# SparkFun_TMC6300_Breakout-BottomJig.net
KiCad netlist of a schematic drawn in EAGLE
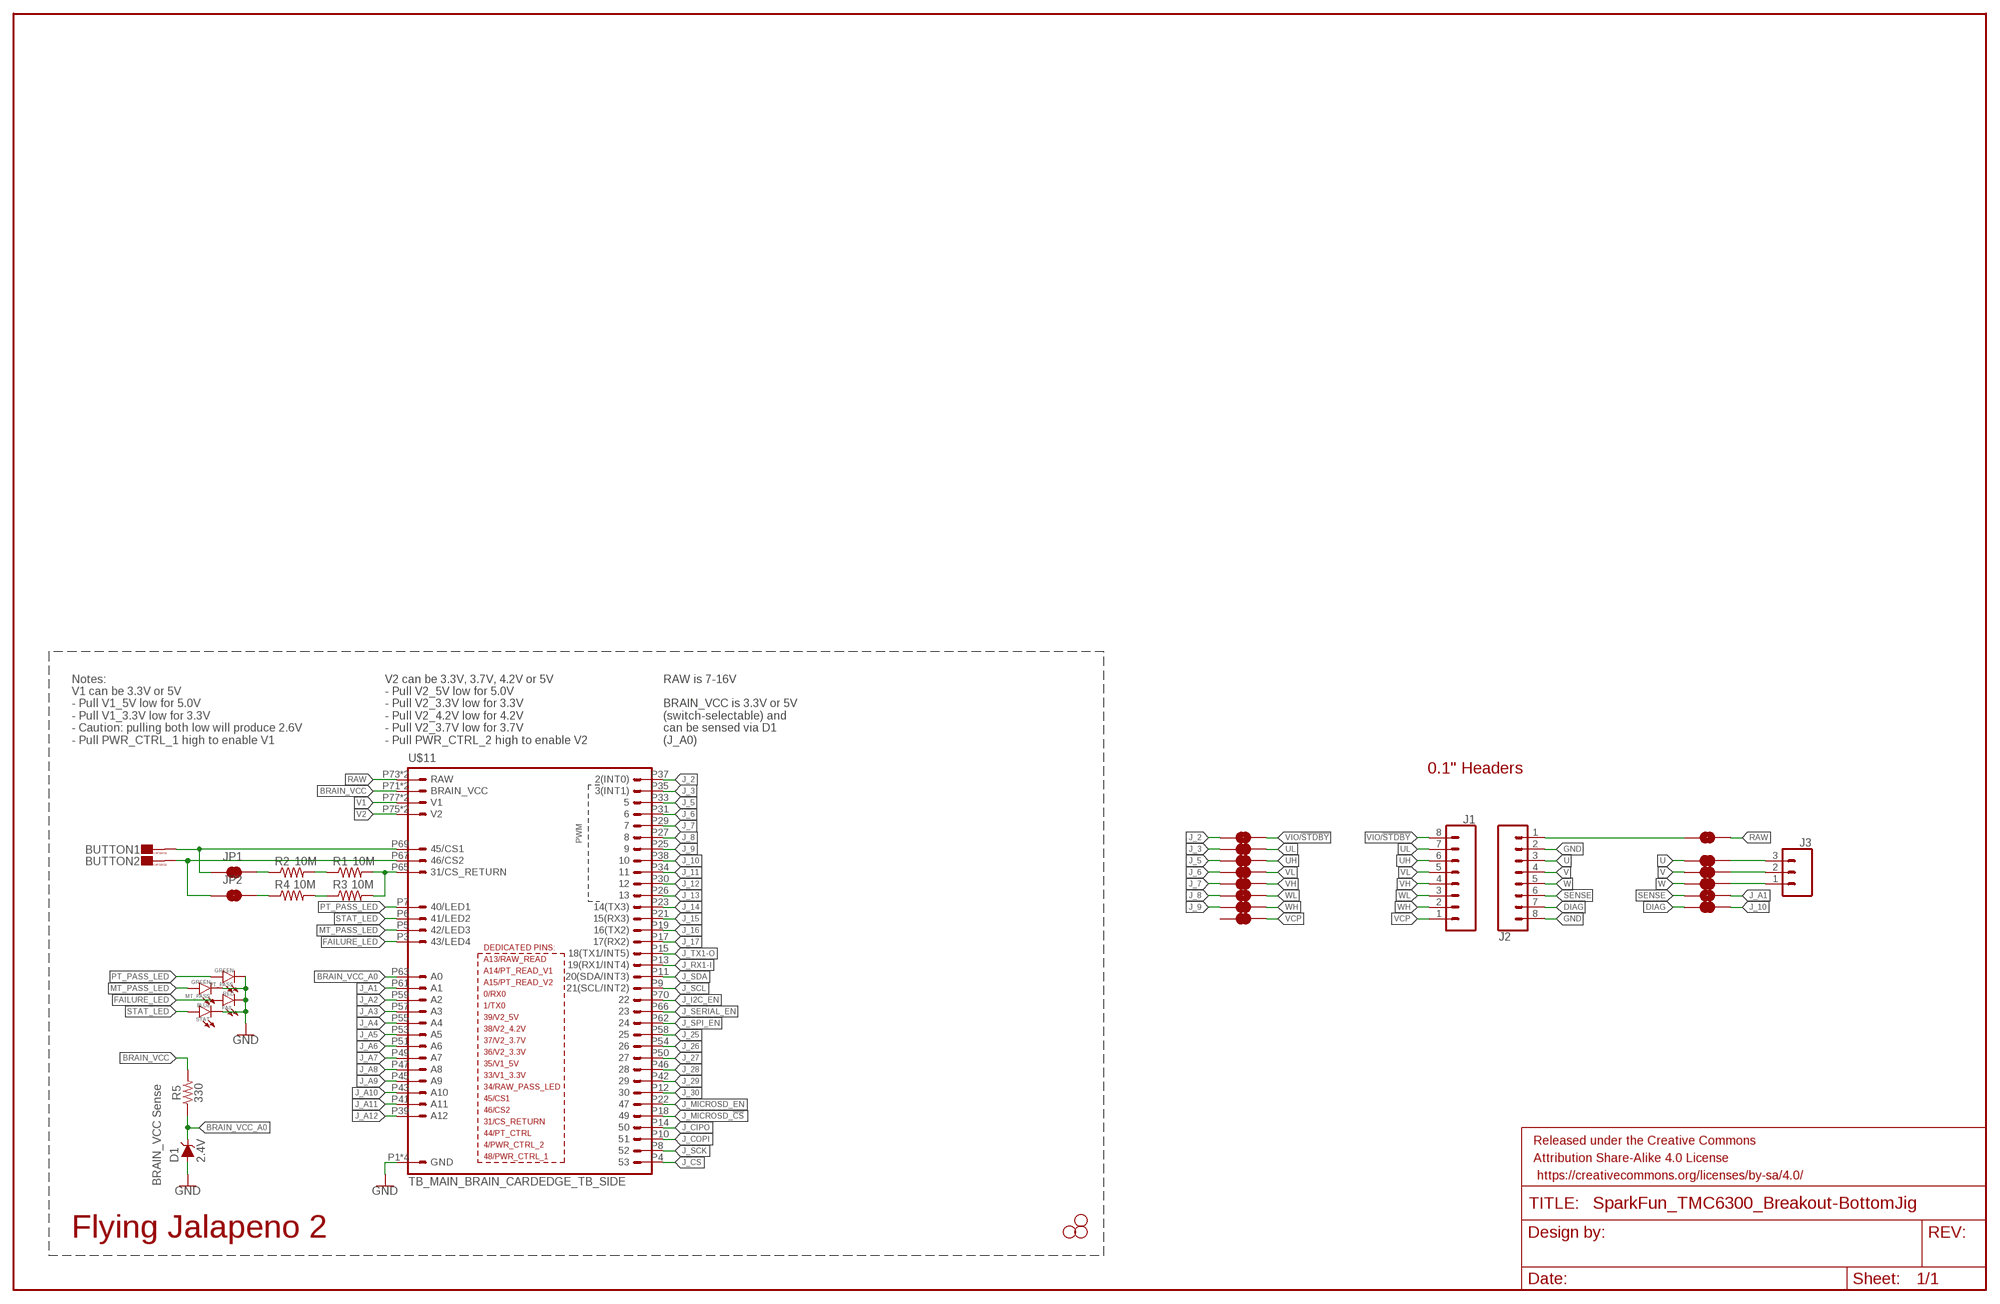
[diagram p0: schematic, sheet 1]

(export (version "E")
  (design (tool "Eeschema 10.0.6"))
  (components
    (comp (ref "BUTTON1")
      (value "CAPSENSE_BUTTON_PAD_ONLYV2_SMALL")
      (footprint "eagle-import:CAPSENSE_BUTTON_PAD_ONLY_SM")
      (libsource (lib "eagle-import") (part "CAPSENSE_BUTTON_PAD_ONLYV2_SMALL"))
    )
    (comp (ref "BUTTON2")
      (value "CAPSENSE_BUTTON_PAD_ONLYV2_SMALL")
      (footprint "eagle-import:CAPSENSE_BUTTON_PAD_ONLY_SM")
      (libsource (lib "eagle-import") (part "CAPSENSE_BUTTON_PAD_ONLYV2_SMALL"))
    )
    (comp (ref "D1")
      (value "2.4V")
      (footprint "eagle-import:SOD-323")
      (fields (field (name "DIGIKEY_PART") "MM3Z2V4T1GOSCT-ND"))
      (libsource (lib "eagle-import") (part "DIODE-ZENER-MM3Z2V4T1G"))
    )
    (comp (ref "FAIL")
      (value "RED")
      (footprint "eagle-import:LED-1206")
      (libsource (lib "eagle-import") (part "LED-RED1206"))
    )
    (comp (ref "FRAME2")
      (value "FRAME-LEDGER")
      (footprint "eagle-import:CREATIVE_COMMONS")
      (libsource (lib "eagle-import") (part "FRAME-LEDGER"))
    )
    (comp (ref "H1")
      (value "STAND-OFF")
      (footprint "eagle-import:STAND-OFF")
      (libsource (lib "eagle-import") (part "STAND-OFF"))
    )
    (comp (ref "H3")
      (value "STAND-OFF")
      (footprint "eagle-import:STAND-OFF")
      (libsource (lib "eagle-import") (part "STAND-OFF"))
    )
    (comp (ref "H4")
      (value "STAND-OFF")
      (footprint "eagle-import:STAND-OFF")
      (libsource (lib "eagle-import") (part "STAND-OFF"))
    )
    (comp (ref "J1")
      (value "CONN_08LOCK_NO_SILK")
      (footprint "eagle-import:1X08_LOCK_NO_SILK")
      (libsource (lib "eagle-import") (part "CONN_08LOCK_NO_SILK"))
    )
    (comp (ref "J2")
      (value "CONN_08LOCK_NO_SILK")
      (footprint "eagle-import:1X08_LOCK_NO_SILK")
      (libsource (lib "eagle-import") (part "CONN_08LOCK_NO_SILK"))
    )
    (comp (ref "J3")
      (value "CONN_031X03_NO_SILK")
      (footprint "eagle-import:1X03_NO_SILK")
      (libsource (lib "eagle-import") (part "CONN_031X03_NO_SILK"))
    )
    (comp (ref "JP1")
      (value "JUMPER-SMT_2_NC_TRACE_SILK")
      (footprint "eagle-import:SMT-JUMPER_2_NC_TRACE_SILK")
      (libsource (lib "eagle-import") (part "JUMPER-SMT_2_NC_TRACE_SILK"))
    )
    (comp (ref "JP2")
      (value "JUMPER-SMT_2_NC_TRACE_SILK")
      (footprint "eagle-import:SMT-JUMPER_2_NC_TRACE_SILK")
      (libsource (lib "eagle-import") (part "JUMPER-SMT_2_NC_TRACE_SILK"))
    )
    (comp (ref "J_SCL6")
      (value "JUMPER-SMT_2_NC_TRACE_NO-SILK")
      (footprint "eagle-import:SMT-JUMPER_2_NC_TRACE_NO-SILK")
      (libsource (lib "eagle-import") (part "JUMPER-SMT_2_NC_TRACE_NO-SILK"))
    )
    (comp (ref "J_SCL7")
      (value "JUMPER-SMT_2_NC_TRACE_NO-SILK")
      (footprint "eagle-import:SMT-JUMPER_2_NC_TRACE_NO-SILK")
      (libsource (lib "eagle-import") (part "JUMPER-SMT_2_NC_TRACE_NO-SILK"))
    )
    (comp (ref "J_SCL8")
      (value "JUMPER-SMT_2_NC_TRACE_NO-SILK")
      (footprint "eagle-import:SMT-JUMPER_2_NC_TRACE_NO-SILK")
      (libsource (lib "eagle-import") (part "JUMPER-SMT_2_NC_TRACE_NO-SILK"))
    )
    (comp (ref "J_SDA1")
      (value "JUMPER-SMT_2_NC_TRACE_NO-SILK")
      (footprint "eagle-import:SMT-JUMPER_2_NC_TRACE_NO-SILK")
      (libsource (lib "eagle-import") (part "JUMPER-SMT_2_NC_TRACE_NO-SILK"))
    )
    (comp (ref "J_SDA2")
      (value "JUMPER-SMT_2_NC_TRACE_NO-SILK")
      (footprint "eagle-import:SMT-JUMPER_2_NC_TRACE_NO-SILK")
      (libsource (lib "eagle-import") (part "JUMPER-SMT_2_NC_TRACE_NO-SILK"))
    )
    (comp (ref "J_SDA3")
      (value "JUMPER-SMT_2_NC_TRACE_NO-SILK")
      (footprint "eagle-import:SMT-JUMPER_2_NC_TRACE_NO-SILK")
      (libsource (lib "eagle-import") (part "JUMPER-SMT_2_NC_TRACE_NO-SILK"))
    )
    (comp (ref "J_SDA4")
      (value "JUMPER-SMT_2_NC_TRACE_NO-SILK")
      (footprint "eagle-import:SMT-JUMPER_2_NC_TRACE_NO-SILK")
      (libsource (lib "eagle-import") (part "JUMPER-SMT_2_NC_TRACE_NO-SILK"))
    )
    (comp (ref "J_SDA5")
      (value "JUMPER-SMT_2_NC_TRACE_NO-SILK")
      (footprint "eagle-import:SMT-JUMPER_2_NC_TRACE_NO-SILK")
      (libsource (lib "eagle-import") (part "JUMPER-SMT_2_NC_TRACE_NO-SILK"))
    )
    (comp (ref "J_SDA6")
      (value "JUMPER-SMT_2_NC_TRACE_NO-SILK")
      (footprint "eagle-import:SMT-JUMPER_2_NC_TRACE_NO-SILK")
      (libsource (lib "eagle-import") (part "JUMPER-SMT_2_NC_TRACE_NO-SILK"))
    )
    (comp (ref "J_SDA7")
      (value "JUMPER-SMT_2_NC_TRACE_NO-SILK")
      (footprint "eagle-import:SMT-JUMPER_2_NC_TRACE_NO-SILK")
      (libsource (lib "eagle-import") (part "JUMPER-SMT_2_NC_TRACE_NO-SILK"))
    )
    (comp (ref "J_SDA8")
      (value "JUMPER-SMT_2_NC_TRACE_NO-SILK")
      (footprint "eagle-import:SMT-JUMPER_2_NC_TRACE_NO-SILK")
      (libsource (lib "eagle-import") (part "JUMPER-SMT_2_NC_TRACE_NO-SILK"))
    )
    (comp (ref "J_SDA9")
      (value "JUMPER-SMT_2_NC_TRACE_NO-SILK")
      (footprint "eagle-import:SMT-JUMPER_2_NC_TRACE_NO-SILK")
      (libsource (lib "eagle-import") (part "JUMPER-SMT_2_NC_TRACE_NO-SILK"))
    )
    (comp (ref "J_SDA10")
      (value "JUMPER-SMT_2_NC_TRACE_NO-SILK")
      (footprint "eagle-import:SMT-JUMPER_2_NC_TRACE_NO-SILK")
      (libsource (lib "eagle-import") (part "JUMPER-SMT_2_NC_TRACE_NO-SILK"))
    )
    (comp (ref "J_SDA11")
      (value "JUMPER-SMT_2_NC_TRACE_NO-SILK")
      (footprint "eagle-import:SMT-JUMPER_2_NC_TRACE_NO-SILK")
      (libsource (lib "eagle-import") (part "JUMPER-SMT_2_NC_TRACE_NO-SILK"))
    )
    (comp (ref "MT_PASS")
      (value "GREEN")
      (footprint "eagle-import:LED-1206")
      (libsource (lib "eagle-import") (part "LED-GREEN1206"))
    )
    (comp (ref "PT_PASS")
      (value "GREEN")
      (footprint "eagle-import:LED-1206")
      (libsource (lib "eagle-import") (part "LED-GREEN1206"))
    )
    (comp (ref "R1")
      (value "10M")
      (footprint "eagle-import:0603")
      (libsource (lib "eagle-import") (part "10MOHM-0603-1/10W-5%"))
    )
    (comp (ref "R2")
      (value "10M")
      (footprint "eagle-import:0603")
      (libsource (lib "eagle-import") (part "10MOHM-0603-1/10W-5%"))
    )
    (comp (ref "R3")
      (value "10M")
      (footprint "eagle-import:0603")
      (libsource (lib "eagle-import") (part "10MOHM-0603-1/10W-5%"))
    )
    (comp (ref "R4")
      (value "10M")
      (footprint "eagle-import:0603")
      (libsource (lib "eagle-import") (part "10MOHM-0603-1/10W-5%"))
    )
    (comp (ref "R5")
      (value "330")
      (footprint "eagle-import:0603")
      (libsource (lib "eagle-import") (part "330OHM-0603-1/10W-1%"))
    )
    (comp (ref "STAT")
      (value "BLUE")
      (footprint "eagle-import:LED-1206")
      (libsource (lib "eagle-import") (part "LED-BLUE1206"))
    )
    (comp (ref "U$11")
      (value "TB_MAIN_BRAIN_CARDEDGE_TB_SIDE")
      (footprint "eagle-import:TB_CARDEDGE")
      (libsource (lib "eagle-import") (part "TB_MAIN_BRAIN_CARDEDGE_TB_SIDE"))
    )
  )
  (nets
    (net (code "1") (name "/J_MICROSD_~{CS}") (class "Default")
      (node (ref "U$11") (pin "P18") (pinfunction "49_P18") (pintype "passive"))
    )
    (net (code "2") (name "/VIO{slash}~{STDBY}") (class "Default")
      (node (ref "J1") (pin "8") (pinfunction "8_8") (pintype "passive"))
      (node (ref "J_SCL8") (pin "2") (pinfunction "2_2") (pintype "passive"))
    )
    (net (code "3") (name "BRAIN_VCC") (class "Default")
      (node (ref "R5") (pin "2") (pinfunction "2_2") (pintype "passive"))
      (node (ref "U$11") (pin "P71") (pinfunction "BRAIN_VCC_P71") (pintype "passive"))
      (node (ref "U$11") (pin "P72") (pinfunction "BRAIN_VCC_P72") (pintype "passive"))
    )
    (net (code "4") (name "BRAIN_VCC_A0") (class "Default")
      (node (ref "D1") (pin "C") (pinfunction "C_C") (pintype "passive"))
      (node (ref "R5") (pin "1") (pinfunction "1_1") (pintype "passive"))
      (node (ref "U$11") (pin "P63") (pinfunction "A0_P63") (pintype "passive"))
    )
    (net (code "5") (name "DIAG") (class "Default")
      (node (ref "J2") (pin "7") (pinfunction "7_7") (pintype "passive"))
      (node (ref "J_SDA7") (pin "1") (pinfunction "1_1") (pintype "passive"))
    )
    (net (code "6") (name "FAILURE_LED") (class "Default")
      (node (ref "FAIL") (pin "A") (pinfunction "A_A") (pintype "passive"))
      (node (ref "U$11") (pin "P3") (pinfunction "43/LED4_P3") (pintype "passive"))
    )
    (net (code "7") (name "GND") (class "Default")
      (node (ref "D1") (pin "A") (pinfunction "A_A") (pintype "passive"))
      (node (ref "FAIL") (pin "C") (pinfunction "C_C") (pintype "passive"))
      (node (ref "J2") (pin "2") (pinfunction "2_2") (pintype "passive"))
      (node (ref "J2") (pin "8") (pinfunction "8_8") (pintype "passive"))
      (node (ref "MT_PASS") (pin "C") (pinfunction "C_C") (pintype "passive"))
      (node (ref "PT_PASS") (pin "C") (pinfunction "C_C") (pintype "passive"))
      (node (ref "STAT") (pin "C") (pinfunction "C_C") (pintype "passive"))
      (node (ref "U$11") (pin "P1") (pinfunction "GND_P1") (pintype "passive"))
      (node (ref "U$11") (pin "P2") (pinfunction "GND_P2") (pintype "passive"))
      (node (ref "U$11") (pin "P79") (pinfunction "GND_P79") (pintype "passive"))
      (node (ref "U$11") (pin "P80") (pinfunction "GND_P80") (pintype "passive"))
    )
    (net (code "8") (name "J_2") (class "Default")
      (node (ref "J_SCL8") (pin "1") (pinfunction "1_1") (pintype "passive"))
      (node (ref "U$11") (pin "P37") (pinfunction "2(INT0)_P37") (pintype "passive"))
    )
    (net (code "9") (name "J_3") (class "Default")
      (node (ref "J_SCL6") (pin "1") (pinfunction "1_1") (pintype "passive"))
      (node (ref "U$11") (pin "P35") (pinfunction "3(INT1)_P35") (pintype "passive"))
    )
    (net (code "10") (name "J_5") (class "Default")
      (node (ref "J_SCL7") (pin "1") (pinfunction "1_1") (pintype "passive"))
      (node (ref "U$11") (pin "P33") (pinfunction "5_P33") (pintype "passive"))
    )
    (net (code "11") (name "J_6") (class "Default")
      (node (ref "J_SDA2") (pin "1") (pinfunction "1_1") (pintype "passive"))
      (node (ref "U$11") (pin "P31") (pinfunction "6_P31") (pintype "passive"))
    )
    (net (code "12") (name "J_7") (class "Default")
      (node (ref "J_SDA3") (pin "1") (pinfunction "1_1") (pintype "passive"))
      (node (ref "U$11") (pin "P29") (pinfunction "7_P29") (pintype "passive"))
    )
    (net (code "13") (name "J_8") (class "Default")
      (node (ref "J_SDA4") (pin "1") (pinfunction "1_1") (pintype "passive"))
      (node (ref "U$11") (pin "P27") (pinfunction "8_P27") (pintype "passive"))
    )
    (net (code "14") (name "J_9") (class "Default")
      (node (ref "J_SDA5") (pin "1") (pinfunction "1_1") (pintype "passive"))
      (node (ref "U$11") (pin "P25") (pinfunction "9_P25") (pintype "passive"))
    )
    (net (code "15") (name "J_10") (class "Default")
      (node (ref "J_SDA7") (pin "2") (pinfunction "2_2") (pintype "passive"))
      (node (ref "U$11") (pin "P38") (pinfunction "10_P38") (pintype "passive"))
    )
    (net (code "16") (name "J_11") (class "Default")
      (node (ref "U$11") (pin "P34") (pinfunction "11_P34") (pintype "passive"))
    )
    (net (code "17") (name "J_12") (class "Default")
      (node (ref "U$11") (pin "P30") (pinfunction "12_P30") (pintype "passive"))
    )
    (net (code "18") (name "J_13") (class "Default")
      (node (ref "U$11") (pin "P26") (pinfunction "13_P26") (pintype "passive"))
    )
    (net (code "19") (name "J_14") (class "Default")
      (node (ref "U$11") (pin "P23") (pinfunction "14(TX3)_P23") (pintype "passive"))
    )
    (net (code "20") (name "J_15") (class "Default")
      (node (ref "U$11") (pin "P21") (pinfunction "15(RX3)_P21") (pintype "passive"))
    )
    (net (code "21") (name "J_16") (class "Default")
      (node (ref "U$11") (pin "P19") (pinfunction "16(TX2)_P19") (pintype "passive"))
    )
    (net (code "22") (name "J_17") (class "Default")
      (node (ref "U$11") (pin "P17") (pinfunction "17(RX2)_P17") (pintype "passive"))
    )
    (net (code "23") (name "J_25") (class "Default")
      (node (ref "U$11") (pin "P58") (pinfunction "25_P58") (pintype "passive"))
    )
    (net (code "24") (name "J_26") (class "Default")
      (node (ref "U$11") (pin "P54") (pinfunction "26_P54") (pintype "passive"))
    )
    (net (code "25") (name "J_27") (class "Default")
      (node (ref "U$11") (pin "P50") (pinfunction "27_P50") (pintype "passive"))
    )
    (net (code "26") (name "J_28") (class "Default")
      (node (ref "U$11") (pin "P46") (pinfunction "28_P46") (pintype "passive"))
    )
    (net (code "27") (name "J_29") (class "Default")
      (node (ref "U$11") (pin "P42") (pinfunction "29_P42") (pintype "passive"))
    )
    (net (code "28") (name "J_30") (class "Default")
      (node (ref "U$11") (pin "P12") (pinfunction "30_P12") (pintype "passive"))
    )
    (net (code "29") (name "J_A1") (class "Default")
      (node (ref "J_SDA8") (pin "2") (pinfunction "2_2") (pintype "passive"))
      (node (ref "U$11") (pin "P61") (pinfunction "A1_P61") (pintype "passive"))
    )
    (net (code "30") (name "J_A2") (class "Default")
      (node (ref "U$11") (pin "P59") (pinfunction "A2_P59") (pintype "passive"))
    )
    (net (code "31") (name "J_A3") (class "Default")
      (node (ref "U$11") (pin "P57") (pinfunction "A3_P57") (pintype "passive"))
    )
    (net (code "32") (name "J_A4") (class "Default")
      (node (ref "U$11") (pin "P55") (pinfunction "A4_P55") (pintype "passive"))
    )
    (net (code "33") (name "J_A5") (class "Default")
      (node (ref "U$11") (pin "P53") (pinfunction "A5_P53") (pintype "passive"))
    )
    (net (code "34") (name "J_A6") (class "Default")
      (node (ref "U$11") (pin "P51") (pinfunction "A6_P51") (pintype "passive"))
    )
    (net (code "35") (name "J_A7") (class "Default")
      (node (ref "U$11") (pin "P49") (pinfunction "A7_P49") (pintype "passive"))
    )
    (net (code "36") (name "J_A8") (class "Default")
      (node (ref "U$11") (pin "P47") (pinfunction "A8_P47") (pintype "passive"))
    )
    (net (code "37") (name "J_A9") (class "Default")
      (node (ref "U$11") (pin "P45") (pinfunction "A9_P45") (pintype "passive"))
    )
    (net (code "38") (name "J_A10") (class "Default")
      (node (ref "U$11") (pin "P43") (pinfunction "A10_P43") (pintype "passive"))
    )
    (net (code "39") (name "J_A11") (class "Default")
      (node (ref "U$11") (pin "P41") (pinfunction "A11_P41") (pintype "passive"))
    )
    (net (code "40") (name "J_A12") (class "Default")
      (node (ref "U$11") (pin "P39") (pinfunction "A12_P39") (pintype "passive"))
    )
    (net (code "41") (name "J_CIPO") (class "Default")
      (node (ref "U$11") (pin "P14") (pinfunction "50_P14") (pintype "passive"))
    )
    (net (code "42") (name "J_COPI") (class "Default")
      (node (ref "U$11") (pin "P10") (pinfunction "51_P10") (pintype "passive"))
    )
    (net (code "43") (name "J_CS") (class "Default")
      (node (ref "U$11") (pin "P4") (pinfunction "53_P4") (pintype "passive"))
    )
    (net (code "44") (name "J_I2C_EN") (class "Default")
      (node (ref "U$11") (pin "P70") (pinfunction "22_P70") (pintype "passive"))
    )
    (net (code "45") (name "J_MICROSD_EN") (class "Default")
      (node (ref "U$11") (pin "P22") (pinfunction "47_P22") (pintype "passive"))
    )
    (net (code "46") (name "J_RX1-I") (class "Default")
      (node (ref "U$11") (pin "P13") (pinfunction "19(RX1/INT4)_P13") (pintype "passive"))
    )
    (net (code "47") (name "J_SCK") (class "Default")
      (node (ref "U$11") (pin "P8") (pinfunction "52_P8") (pintype "passive"))
    )
    (net (code "48") (name "J_SCL") (class "Default")
      (node (ref "U$11") (pin "P9") (pinfunction "21(SCL/INT2)_P9") (pintype "passive"))
    )
    (net (code "49") (name "J_SDA") (class "Default")
      (node (ref "U$11") (pin "P11") (pinfunction "20(SDA/INT3)_P11") (pintype "passive"))
    )
    (net (code "50") (name "J_SERIAL_EN") (class "Default")
      (node (ref "U$11") (pin "P66") (pinfunction "23_P66") (pintype "passive"))
    )
    (net (code "51") (name "J_SPI_EN") (class "Default")
      (node (ref "U$11") (pin "P62") (pinfunction "24_P62") (pintype "passive"))
    )
    (net (code "52") (name "J_TX1-O") (class "Default")
      (node (ref "U$11") (pin "P15") (pinfunction "18(TX1/INT5)_P15") (pintype "passive"))
    )
    (net (code "53") (name "MT_PASS_LED") (class "Default")
      (node (ref "MT_PASS") (pin "A") (pinfunction "A_A") (pintype "passive"))
      (node (ref "U$11") (pin "P5") (pinfunction "42/LED3_P5") (pintype "passive"))
    )
    (net (code "54") (name "Net-(BUTTON1-CAPSENSE)") (class "Default")
      (node (ref "BUTTON1") (pin "CAPSENSE_PAD") (pinfunction "CAPSENSE_CAPSENSE_PAD") (pintype "bidirectional"))
      (node (ref "JP1") (pin "1") (pinfunction "1_1") (pintype "passive"))
      (node (ref "U$11") (pin "P69") (pinfunction "45/CS1_P69") (pintype "passive"))
    )
    (net (code "55") (name "Net-(BUTTON2-CAPSENSE)") (class "Default")
      (node (ref "BUTTON2") (pin "CAPSENSE_PAD") (pinfunction "CAPSENSE_CAPSENSE_PAD") (pintype "bidirectional"))
      (node (ref "JP2") (pin "1") (pinfunction "1_1") (pintype "passive"))
      (node (ref "U$11") (pin "P67") (pinfunction "46/CS2_P67") (pintype "passive"))
    )
    (net (code "56") (name "Net-(J2-Pad1)") (class "Default")
      (node (ref "J2") (pin "1") (pinfunction "1_1") (pintype "passive"))
      (node (ref "J_SDA1") (pin "1") (pinfunction "1_1") (pintype "passive"))
    )
    (net (code "57") (name "Net-(J3-Pad1)") (class "Default")
      (node (ref "J3") (pin "1") (pinfunction "1_1") (pintype "passive"))
      (node (ref "J_SDA9") (pin "2") (pinfunction "2_2") (pintype "passive"))
    )
    (net (code "58") (name "Net-(J3-Pad2)") (class "Default")
      (node (ref "J3") (pin "2") (pinfunction "2_2") (pintype "passive"))
      (node (ref "J_SDA10") (pin "2") (pinfunction "2_2") (pintype "passive"))
    )
    (net (code "59") (name "Net-(J3-Pad3)") (class "Default")
      (node (ref "J3") (pin "3") (pinfunction "3_3") (pintype "passive"))
      (node (ref "J_SDA11") (pin "2") (pinfunction "2_2") (pintype "passive"))
    )
    (net (code "60") (name "Net-(JP1-Pad2)") (class "Default")
      (node (ref "JP1") (pin "2") (pinfunction "2_2") (pintype "passive"))
      (node (ref "R2") (pin "1") (pinfunction "1_1") (pintype "passive"))
    )
    (net (code "61") (name "Net-(JP2-Pad2)") (class "Default")
      (node (ref "JP2") (pin "2") (pinfunction "2_2") (pintype "passive"))
      (node (ref "R4") (pin "1") (pinfunction "1_1") (pintype "passive"))
    )
    (net (code "62") (name "Net-(R1-Pad1)") (class "Default")
      (node (ref "R1") (pin "1") (pinfunction "1_1") (pintype "passive"))
      (node (ref "R2") (pin "2") (pinfunction "2_2") (pintype "passive"))
    )
    (net (code "63") (name "Net-(R3-Pad1)") (class "Default")
      (node (ref "R3") (pin "1") (pinfunction "1_1") (pintype "passive"))
      (node (ref "R4") (pin "2") (pinfunction "2_2") (pintype "passive"))
    )
    (net (code "64") (name "Net-(U$11-31{slash}CS_RETURN)") (class "Default")
      (node (ref "R1") (pin "2") (pinfunction "2_2") (pintype "passive"))
      (node (ref "R3") (pin "2") (pinfunction "2_2") (pintype "passive"))
      (node (ref "U$11") (pin "P65") (pinfunction "31/CS_RETURN_P65") (pintype "passive"))
    )
    (net (code "65") (name "PT_PASS_LED") (class "Default")
      (node (ref "PT_PASS") (pin "A") (pinfunction "A_A") (pintype "passive"))
      (node (ref "U$11") (pin "P7") (pinfunction "40/LED1_P7") (pintype "passive"))
    )
    (net (code "66") (name "RAW") (class "Default")
      (node (ref "J_SDA1") (pin "2") (pinfunction "2_2") (pintype "passive"))
      (node (ref "U$11") (pin "P73") (pinfunction "RAW_P73") (pintype "passive"))
      (node (ref "U$11") (pin "P74") (pinfunction "RAW_P74") (pintype "passive"))
    )
    (net (code "67") (name "SENSE") (class "Default")
      (node (ref "J2") (pin "6") (pinfunction "6_6") (pintype "passive"))
      (node (ref "J_SDA8") (pin "1") (pinfunction "1_1") (pintype "passive"))
    )
    (net (code "68") (name "STAT_LED") (class "Default")
      (node (ref "STAT") (pin "A") (pinfunction "A_A") (pintype "passive"))
      (node (ref "U$11") (pin "P6") (pinfunction "41/LED2_P6") (pintype "passive"))
    )
    (net (code "69") (name "U") (class "Default")
      (node (ref "J2") (pin "3") (pinfunction "3_3") (pintype "passive"))
      (node (ref "J_SDA11") (pin "1") (pinfunction "1_1") (pintype "passive"))
    )
    (net (code "70") (name "UH") (class "Default")
      (node (ref "J1") (pin "6") (pinfunction "6_6") (pintype "passive"))
      (node (ref "J_SCL7") (pin "2") (pinfunction "2_2") (pintype "passive"))
    )
    (net (code "71") (name "UL") (class "Default")
      (node (ref "J1") (pin "7") (pinfunction "7_7") (pintype "passive"))
      (node (ref "J_SCL6") (pin "2") (pinfunction "2_2") (pintype "passive"))
    )
    (net (code "72") (name "V") (class "Default")
      (node (ref "J2") (pin "4") (pinfunction "4_4") (pintype "passive"))
      (node (ref "J_SDA10") (pin "1") (pinfunction "1_1") (pintype "passive"))
    )
    (net (code "73") (name "V1") (class "Default")
      (node (ref "U$11") (pin "P77") (pinfunction "V1_P77") (pintype "passive"))
      (node (ref "U$11") (pin "P78") (pinfunction "V1_P78") (pintype "passive"))
    )
    (net (code "74") (name "V2") (class "Default")
      (node (ref "U$11") (pin "P75") (pinfunction "V2_P75") (pintype "passive"))
      (node (ref "U$11") (pin "P76") (pinfunction "V2_P76") (pintype "passive"))
    )
    (net (code "75") (name "VCP") (class "Default")
      (node (ref "J1") (pin "1") (pinfunction "1_1") (pintype "passive"))
      (node (ref "J_SDA6") (pin "2") (pinfunction "2_2") (pintype "passive"))
    )
    (net (code "76") (name "VH") (class "Default")
      (node (ref "J1") (pin "4") (pinfunction "4_4") (pintype "passive"))
      (node (ref "J_SDA3") (pin "2") (pinfunction "2_2") (pintype "passive"))
    )
    (net (code "77") (name "VL") (class "Default")
      (node (ref "J1") (pin "5") (pinfunction "5_5") (pintype "passive"))
      (node (ref "J_SDA2") (pin "2") (pinfunction "2_2") (pintype "passive"))
    )
    (net (code "78") (name "W") (class "Default")
      (node (ref "J2") (pin "5") (pinfunction "5_5") (pintype "passive"))
      (node (ref "J_SDA9") (pin "1") (pinfunction "1_1") (pintype "passive"))
    )
    (net (code "79") (name "WH") (class "Default")
      (node (ref "J1") (pin "2") (pinfunction "2_2") (pintype "passive"))
      (node (ref "J_SDA5") (pin "2") (pinfunction "2_2") (pintype "passive"))
    )
    (net (code "80") (name "WL") (class "Default")
      (node (ref "J1") (pin "3") (pinfunction "3_3") (pintype "passive"))
      (node (ref "J_SDA4") (pin "2") (pinfunction "2_2") (pintype "passive"))
    )
    (net (code "81") (name "unconnected-(J_SDA6-Pad1)") (class "Default")
      (node (ref "J_SDA6") (pin "1") (pinfunction "1_1") (pintype "passive"))
    )
  )
)
